# WLAN_BLUETOOTH.net
KiCad netlist of a schematic drawn in Altium Designer
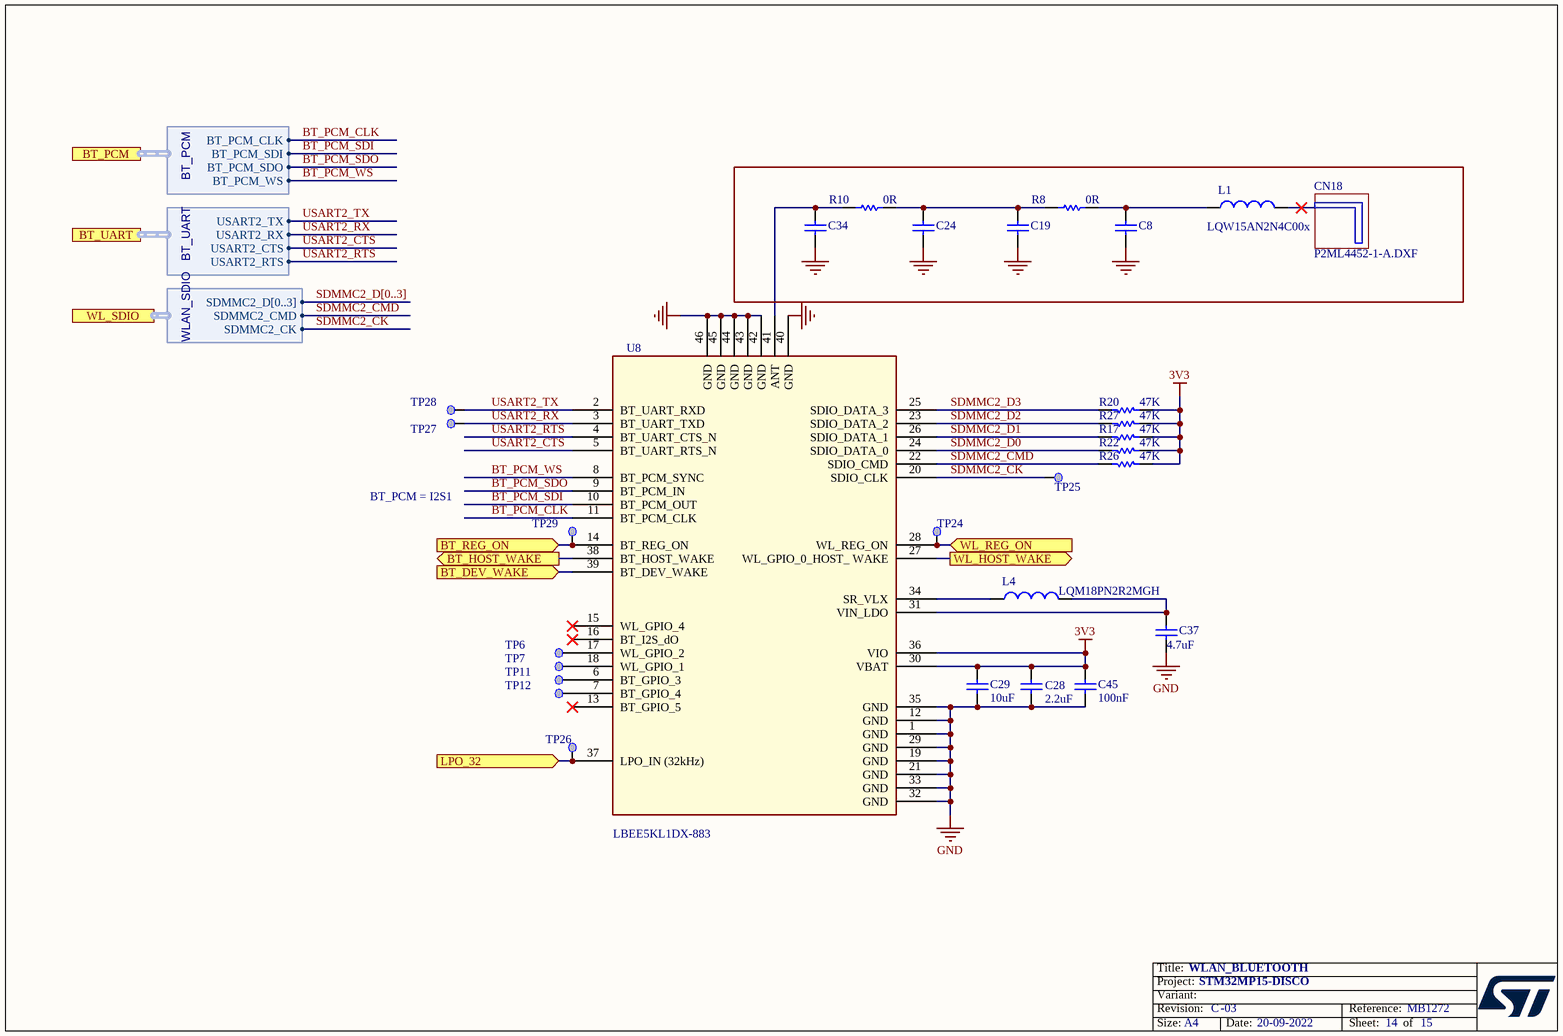
[diagram p0: WLAN_BLUETOOTH.SchDoc]

(export (version "E")
  (design (tool "Eeschema 10.0.6"))
  (components
    (comp (ref "C8")
      (value "Capacitor")
      (footprint "C0402")
      (description "Capacitor, MLCC, 12pF, 50V, NPO, 5%, 0402, T=0,5mm")
      (fields
        (field (name "INTERNAL_PART_NUMBER") "MCD-00200")
        (field (name "MANUFACTURER_PART_NUMBER") "CC0402JRNPO9BN120")
        (field (name "PROVIDED_BY") "SUBCO")
      )
      (libsource (lib "MCD_PARTS_database") (part "Capacitor"))
    )
    (comp (ref "C19")
      (value "Capacitor")
      (footprint "C0402")
      (description "Capacitor, MLCC, 12pF, 50V, NPO, 5%, 0402, T=0,5mm")
      (fields
        (field (name "INTERNAL_PART_NUMBER") "MCD-00200")
        (field (name "MANUFACTURER_PART_NUMBER") "CC0402JRNPO9BN120")
        (field (name "PROVIDED_BY") "SUBCO")
      )
      (libsource (lib "MCD_PARTS_database") (part "Capacitor"))
    )
    (comp (ref "C24")
      (value "Capacitor")
      (footprint "C0402")
      (description "Capacitor, MLCC, 12pF, 50V, NPO, 5%, 0402, T=0,5mm")
      (fields
        (field (name "INTERNAL_PART_NUMBER") "MCD-00200")
        (field (name "MANUFACTURER_PART_NUMBER") "CC0402JRNPO9BN120")
        (field (name "PROVIDED_BY") "SUBCO")
      )
      (libsource (lib "MCD_PARTS_database") (part "Capacitor"))
    )
    (comp (ref "C28")
      (value "2.2uF")
      (footprint "C0603")
      (description "Capacitor, MLCC, 2.2uF, 10V, X5R, 10%, 0603, T=0,8mm")
      (fields
        (field (name "INTERNAL_PART_NUMBER") "MCD-00012")
        (field (name "MANUFACTURER_PART_NUMBER") "CC0603KRX5R6BB225")
        (field (name "PROVIDED_BY") "SUBCO")
      )
      (libsource (lib "MCD_PARTS_database") (part "Capacitor"))
    )
    (comp (ref "C29")
      (value "10uF")
      (footprint "C0603")
      (description "Capacitor, MLCC, 10uF, 10V, X5R, 10%, 0603, T=0,8mm")
      (fields
        (field (name "INTERNAL_PART_NUMBER") "MCD-00099")
        (field (name "MANUFACTURER_PART_NUMBER") "GRM188R61A106KE69D")
        (field (name "PROVIDED_BY") "SUBCO")
      )
      (libsource (lib "MCD_PARTS_database") (part "Capacitor"))
    )
    (comp (ref "C34")
      (value "Capacitor")
      (footprint "C0402")
      (description "Capacitor, MLCC, 12pF, 50V, NPO, 5%, 0402, T=0,5mm")
      (fields
        (field (name "INTERNAL_PART_NUMBER") "MCD-00200")
        (field (name "MANUFACTURER_PART_NUMBER") "CC0402JRNPO9BN120")
        (field (name "PROVIDED_BY") "SUBCO")
      )
      (libsource (lib "MCD_PARTS_database") (part "Capacitor"))
    )
    (comp (ref "C37")
      (value "4.7uF")
      (footprint "C0402")
      (description "Capacitor, MLCC, 4.7uF, 6V3, X5R, 20%, 0402, T=0,5mm")
      (fields
        (field (name "INTERNAL_PART_NUMBER") "MCD-01356")
        (field (name "MANUFACTURER_PART_NUMBER") "GRM155R60J475ME47")
        (field (name "PROVIDED_BY") "SUBCO")
      )
      (libsource (lib "MCD_PARTS_database") (part "Capacitor"))
    )
    (comp (ref "C45")
      (value "100nF")
      (footprint "C0402")
      (description "Capacitor,100nF,16V,X7R,10%,0402")
      (fields
        (field (name "INTERNAL_PART_NUMBER") "MCD-00006")
        (field (name "MANUFACTURER_PART_NUMBER") "CC0402KRX7R7BB104")
        (field (name "PROVIDED_BY") "SUBCO")
      )
      (libsource (lib "MCD_PARTS_database") (part "Capacitor"))
    )
    (comp (ref "CN18")
      (value "P2ML4452-1-A.DXF")
      (footprint "ANT_MURATA_TYPE-1-DX_P2ML4452-1-A_DXF")
      (description "Murata_Type1DX_AntennaDesign_P2ML4452-1-A.DXF")
      (fields
        (field (name "INTERNAL_PART_NUMBER") "MCD-00656")
        (field (name "MANUFACTURER_PART_NUMBER") "Antenna design")
      )
      (libsource (lib "MCD_PARTS_database") (part "antenna_Wifi_BLE_Murata"))
    )
    (comp (ref "L1")
      (value "LQW15AN2N4C00x")
      (footprint "IND_0402_MURATA_LQW15AN2N4C00X")
      (description "Inductor,2.4nH,+-0.2nH,0.05R,0.85A,0402")
      (fields
        (field (name "INTERNAL_PART_NUMBER") "MCD-00657")
        (field (name "MANUFACTURER") "MURATA")
        (field (name "PROVIDED_BY") "SUBCO")
      )
      (libsource (lib "MCD_PARTS_database") (part "Inductor"))
    )
    (comp (ref "L4")
      (value "LQM18PN2R2MGH")
      (footprint "L0603")
      (description "Inductor, 2.2µH, 20%, Isat 0.35A, DCR 0.2Ohm, 0603")
      (fields
        (field (name "INTERNAL_PART_NUMBER") "MCD-00659")
        (field (name "MANUFACTURER") "MURATA")
        (field (name "PROVIDED_BY") "SUBCO")
      )
      (libsource (lib "MCD_PARTS_database") (part "Inductor"))
    )
    (comp (ref "R8")
      (value "0R")
      (footprint "R0402")
      (description "Resistor,0R,0402,5%,1/16W")
      (fields
        (field (name "INTERNAL_PART_NUMBER") "MCD-00052")
        (field (name "MANUFACTURER_PART_NUMBER") "RC0402JR-070RL")
        (field (name "PROVIDED_BY") "SUBCO")
      )
      (libsource (lib "MCD_PARTS_database") (part "Resistor"))
    )
    (comp (ref "R10")
      (value "0R")
      (footprint "R0402")
      (description "Resistor,0R,0402,5%,1/16W")
      (fields
        (field (name "INTERNAL_PART_NUMBER") "MCD-00052")
        (field (name "MANUFACTURER_PART_NUMBER") "RC0402JR-070RL")
        (field (name "PROVIDED_BY") "SUBCO")
      )
      (libsource (lib "MCD_PARTS_database") (part "Resistor"))
    )
    (comp (ref "R17")
      (value "47K")
      (footprint "R0402")
      (description "Resistor,47K,0402,1%,1/16W")
      (fields
        (field (name "INTERNAL_PART_NUMBER") "MCD-00063")
        (field (name "MANUFACTURER_PART_NUMBER") "RC0402FR-0747KL")
        (field (name "PROVIDED_BY") "SUBCO")
      )
      (libsource (lib "MCD_PARTS_database") (part "Resistor"))
    )
    (comp (ref "R20")
      (value "47K")
      (footprint "R0402")
      (description "Resistor,47K,0402,1%,1/16W")
      (fields
        (field (name "INTERNAL_PART_NUMBER") "MCD-00063")
        (field (name "MANUFACTURER_PART_NUMBER") "RC0402FR-0747KL")
        (field (name "PROVIDED_BY") "SUBCO")
      )
      (libsource (lib "MCD_PARTS_database") (part "Resistor"))
    )
    (comp (ref "R22")
      (value "47K")
      (footprint "R0402")
      (description "Resistor,47K,0402,1%,1/16W")
      (fields
        (field (name "INTERNAL_PART_NUMBER") "MCD-00063")
        (field (name "MANUFACTURER_PART_NUMBER") "RC0402FR-0747KL")
        (field (name "PROVIDED_BY") "SUBCO")
      )
      (libsource (lib "MCD_PARTS_database") (part "Resistor"))
    )
    (comp (ref "R26")
      (value "47K")
      (footprint "R0402")
      (description "Resistor,47K,0402,1%,1/16W")
      (fields
        (field (name "INTERNAL_PART_NUMBER") "MCD-00063")
        (field (name "MANUFACTURER_PART_NUMBER") "RC0402FR-0747KL")
        (field (name "PROVIDED_BY") "SUBCO")
      )
      (libsource (lib "MCD_PARTS_database") (part "Resistor"))
    )
    (comp (ref "R27")
      (value "47K")
      (footprint "R0402")
      (description "Resistor,47K,0402,1%,1/16W")
      (fields
        (field (name "INTERNAL_PART_NUMBER") "MCD-00063")
        (field (name "MANUFACTURER_PART_NUMBER") "RC0402FR-0747KL")
        (field (name "PROVIDED_BY") "SUBCO")
      )
      (libsource (lib "MCD_PARTS_database") (part "Resistor"))
    )
    (comp (ref "TP6")
      (value "Test Point")
      (footprint "TP_SMD_1MM")
      (description "Test Point 1mm")
      (fields
        (field (name "INTERNAL_PART_NUMBER") "MCD-00074")
        (field (name "MANUFACTURER_PART_NUMBER") "n/a")
      )
      (libsource (lib "MCD_PARTS_database") (part "Test Point"))
    )
    (comp (ref "TP7")
      (value "Test Point")
      (footprint "TP_SMD_1MM")
      (description "Test Point 1mm")
      (fields
        (field (name "INTERNAL_PART_NUMBER") "MCD-00074")
        (field (name "MANUFACTURER_PART_NUMBER") "n/a")
      )
      (libsource (lib "MCD_PARTS_database") (part "Test Point"))
    )
    (comp (ref "TP11")
      (value "Test Point")
      (footprint "TP_SMD_1MM")
      (description "Test Point 1mm")
      (fields
        (field (name "INTERNAL_PART_NUMBER") "MCD-00074")
        (field (name "MANUFACTURER_PART_NUMBER") "n/a")
      )
      (libsource (lib "MCD_PARTS_database") (part "Test Point"))
    )
    (comp (ref "TP12")
      (value "Test Point")
      (footprint "TP_SMD_1MM")
      (description "Test Point 1mm")
      (fields
        (field (name "INTERNAL_PART_NUMBER") "MCD-00074")
        (field (name "MANUFACTURER_PART_NUMBER") "n/a")
      )
      (libsource (lib "MCD_PARTS_database") (part "Test Point"))
    )
    (comp (ref "TP24")
      (value "Test Point")
      (footprint "TP_SMD_0-6MM")
      (description "Test Point 0.6mm")
      (fields (field (name "INTERNAL_PART_NUMBER") "MCD-00631"))
      (libsource (lib "") (part "Test Point_1"))
    )
    (comp (ref "TP25")
      (value "Test Point")
      (footprint "TP_SMD_0-6MM")
      (description "Test Point 0.6mm")
      (fields (field (name "INTERNAL_PART_NUMBER") "MCD-00631"))
      (libsource (lib "") (part "Test Point_2"))
    )
    (comp (ref "TP26")
      (value "Test Point")
      (footprint "TP_SMD_0-6MM")
      (description "Test Point 0.6mm")
      (fields (field (name "INTERNAL_PART_NUMBER") "MCD-00631"))
      (libsource (lib "") (part "Test Point_1"))
    )
    (comp (ref "TP27")
      (value "Test Point")
      (footprint "TP_SMD_0-6MM")
      (description "Test Point 0.6mm")
      (fields (field (name "INTERNAL_PART_NUMBER") "MCD-00631"))
      (libsource (lib "MCD_PARTS_database") (part "Test Point"))
    )
    (comp (ref "TP28")
      (value "Test Point")
      (footprint "TP_SMD_0-6MM")
      (description "Test Point 0.6mm")
      (fields (field (name "INTERNAL_PART_NUMBER") "MCD-00631"))
      (libsource (lib "MCD_PARTS_database") (part "Test Point"))
    )
    (comp (ref "TP29")
      (value "Test Point")
      (footprint "TP_SMD_0-6MM")
      (description "Test Point 0.6mm")
      (fields (field (name "INTERNAL_PART_NUMBER") "MCD-00631"))
      (libsource (lib "") (part "Test Point_1"))
    )
    (comp (ref "U8")
      (value "LBEE5KL1DX-883")
      (footprint "MOD_WLAN-BT_MURATA_LBEE5KL1DX-883")
      (description "IEEE802.11b/g/n W-LAN + Bluetooth 4.1+EDR module")
      (fields
        (field (name "INTERNAL_PART_NUMBER") "MCD-00268")
        (field (name "MANUFACTURER") "MURATA")
        (field (name "PROVIDED_BY") "SUBCO")
      )
      (libsource (lib "MCD_PARTS_database") (part "LBEE5KL1DX-883"))
    )
  )
  (nets
    (net (code "4") (name "/BT_DEV_WAKE") (class "Default")
      (node (ref "U8") (pin "39") (pinfunction "BT_DEV_WAKE_39") (pintype "passive"))
    )
    (net (code "5") (name "/BT_HOST_WAKE") (class "Default")
      (node (ref "U8") (pin "38") (pinfunction "BT_HOST_WAKE_38") (pintype "passive"))
    )
    (net (code "6") (name "/BT_PCM_CLK") (class "Default")
      (node (ref "U8") (pin "11") (pinfunction "BT_PCM_CLK_11") (pintype "passive"))
    )
    (net (code "7") (name "/BT_PCM_SDI") (class "Default")
      (node (ref "U8") (pin "10") (pinfunction "BT_PCM_OUT_10") (pintype "passive"))
    )
    (net (code "8") (name "/BT_PCM_SDO") (class "Default")
      (node (ref "U8") (pin "9") (pinfunction "BT_PCM_IN_9") (pintype "passive"))
    )
    (net (code "9") (name "/BT_PCM_WS") (class "Default")
      (node (ref "U8") (pin "8") (pinfunction "BT_PCM_SYNC_8") (pintype "passive"))
    )
    (net (code "10") (name "/BT_REG_ON") (class "Default")
      (node (ref "TP29") (pin "1") (pinfunction "1_1") (pintype "passive"))
      (node (ref "U8") (pin "14") (pinfunction "BT_REG_ON_14") (pintype "passive"))
    )
    (net (code "11") (name "/LPO_32") (class "Default")
      (node (ref "TP26") (pin "1") (pinfunction "1_1") (pintype "passive"))
      (node (ref "U8") (pin "37") (pinfunction "LPO_IN_(32kHz)_37") (pintype "passive"))
    )
    (net (code "12") (name "/SDMMC2_CK") (class "Default")
      (node (ref "TP25") (pin "1") (pinfunction "1_1") (pintype "passive"))
      (node (ref "U8") (pin "20") (pinfunction "SDIO_CLK_20") (pintype "passive"))
    )
    (net (code "13") (name "/SDMMC2_CMD") (class "Default")
      (node (ref "R26") (pin "2") (pinfunction "2_2") (pintype "passive"))
      (node (ref "U8") (pin "22") (pinfunction "SDIO_CMD_22") (pintype "passive"))
    )
    (net (code "14") (name "/SDMMC2_D0") (class "Default")
      (node (ref "R22") (pin "2") (pinfunction "2_2") (pintype "passive"))
      (node (ref "U8") (pin "24") (pinfunction "SDIO_DATA_0_24") (pintype "passive"))
    )
    (net (code "15") (name "/SDMMC2_D1") (class "Default")
      (node (ref "R17") (pin "2") (pinfunction "2_2") (pintype "passive"))
      (node (ref "U8") (pin "26") (pinfunction "SDIO_DATA_1_26") (pintype "passive"))
    )
    (net (code "16") (name "/SDMMC2_D2") (class "Default")
      (node (ref "R27") (pin "2") (pinfunction "2_2") (pintype "passive"))
      (node (ref "U8") (pin "23") (pinfunction "SDIO_DATA_2_23") (pintype "passive"))
    )
    (net (code "17") (name "/SDMMC2_D3") (class "Default")
      (node (ref "R20") (pin "2") (pinfunction "2_2") (pintype "passive"))
      (node (ref "U8") (pin "25") (pinfunction "SDIO_DATA_3_25") (pintype "passive"))
    )
    (net (code "19") (name "/USART2_CTS") (class "Default")
      (node (ref "U8") (pin "5") (pinfunction "BT_UART_RTS_N_5") (pintype "passive"))
    )
    (net (code "20") (name "/USART2_RTS") (class "Default")
      (node (ref "U8") (pin "4") (pinfunction "BT_UART_CTS_N_4") (pintype "passive"))
    )
    (net (code "21") (name "/USART2_RX") (class "Default")
      (node (ref "TP27") (pin "1") (pinfunction "1_1") (pintype "passive"))
      (node (ref "U8") (pin "3") (pinfunction "BT_UART_TXD_3") (pintype "passive"))
    )
    (net (code "22") (name "/USART2_TX") (class "Default")
      (node (ref "TP28") (pin "1") (pinfunction "1_1") (pintype "passive"))
      (node (ref "U8") (pin "2") (pinfunction "BT_UART_RXD_2") (pintype "passive"))
    )
    (net (code "23") (name "/WL_HOST_WAKE") (class "Default")
      (node (ref "U8") (pin "27") (pinfunction "WL_GPIO_0_HOST__WAKE_27") (pintype "passive"))
    )
    (net (code "24") (name "/WL_REG_ON") (class "Default")
      (node (ref "TP24") (pin "1") (pinfunction "1_1") (pintype "passive"))
      (node (ref "U8") (pin "28") (pinfunction "WL_REG_ON_28") (pintype "passive"))
    )
    (net (code "28") (name "3V3") (class "Default")
      (node (ref "C28") (pin "2") (pinfunction "2_2") (pintype "passive"))
      (node (ref "C29") (pin "2") (pinfunction "2_2") (pintype "passive"))
      (node (ref "C45") (pin "2") (pinfunction "2_2") (pintype "passive"))
      (node (ref "R17") (pin "1") (pinfunction "1_1") (pintype "passive"))
      (node (ref "R20") (pin "1") (pinfunction "1_1") (pintype "passive"))
      (node (ref "R22") (pin "1") (pinfunction "1_1") (pintype "passive"))
      (node (ref "R26") (pin "1") (pinfunction "1_1") (pintype "passive"))
      (node (ref "R27") (pin "1") (pinfunction "1_1") (pintype "passive"))
      (node (ref "U8") (pin "30") (pinfunction "VBAT_30") (pintype "passive"))
      (node (ref "U8") (pin "36") (pinfunction "VIO_36") (pintype "passive"))
    )
    (net (code "29") (name "GND") (class "Default")
      (node (ref "C19") (pin "1") (pinfunction "1_1") (pintype "passive"))
      (node (ref "C24") (pin "1") (pinfunction "1_1") (pintype "passive"))
      (node (ref "C28") (pin "1") (pinfunction "1_1") (pintype "passive"))
      (node (ref "C29") (pin "1") (pinfunction "1_1") (pintype "passive"))
      (node (ref "C34") (pin "1") (pinfunction "1_1") (pintype "passive"))
      (node (ref "C37") (pin "1") (pinfunction "1_1") (pintype "passive"))
      (node (ref "C45") (pin "1") (pinfunction "1_1") (pintype "passive"))
      (node (ref "C8") (pin "1") (pinfunction "1_1") (pintype "passive"))
      (node (ref "U8") (pin "1") (pinfunction "GND_1") (pintype "passive"))
      (node (ref "U8") (pin "12") (pinfunction "GND_12") (pintype "passive"))
      (node (ref "U8") (pin "19") (pinfunction "GND_19") (pintype "passive"))
      (node (ref "U8") (pin "21") (pinfunction "GND_21") (pintype "passive"))
      (node (ref "U8") (pin "29") (pinfunction "GND_29") (pintype "passive"))
      (node (ref "U8") (pin "32") (pinfunction "GND_32") (pintype "passive"))
      (node (ref "U8") (pin "33") (pinfunction "GND_33") (pintype "passive"))
      (node (ref "U8") (pin "35") (pinfunction "GND_35") (pintype "passive"))
      (node (ref "U8") (pin "40") (pinfunction "GND_40") (pintype "passive"))
      (node (ref "U8") (pin "42") (pinfunction "GND_42") (pintype "passive"))
      (node (ref "U8") (pin "43") (pinfunction "GND_43") (pintype "passive"))
      (node (ref "U8") (pin "44") (pinfunction "GND_44") (pintype "passive"))
      (node (ref "U8") (pin "45") (pinfunction "GND_45") (pintype "passive"))
      (node (ref "U8") (pin "46") (pinfunction "GND_46") (pintype "passive"))
    )
    (net (code "30") (name "Net-(C8-Pad2)") (class "Default")
      (node (ref "C8") (pin "2") (pinfunction "2_2") (pintype "passive"))
      (node (ref "L1") (pin "1") (pinfunction "1_1") (pintype "passive"))
      (node (ref "R8") (pin "1") (pinfunction "1_1") (pintype "passive"))
    )
    (net (code "31") (name "Net-(C19-Pad2)") (class "Default")
      (node (ref "C19") (pin "2") (pinfunction "2_2") (pintype "passive"))
      (node (ref "C24") (pin "2") (pinfunction "2_2") (pintype "passive"))
      (node (ref "R10") (pin "1") (pinfunction "1_1") (pintype "passive"))
      (node (ref "R8") (pin "2") (pinfunction "2_2") (pintype "passive"))
    )
    (net (code "32") (name "Net-(U8-ANT)") (class "Default")
      (node (ref "C34") (pin "2") (pinfunction "2_2") (pintype "passive"))
      (node (ref "R10") (pin "2") (pinfunction "2_2") (pintype "passive"))
      (node (ref "U8") (pin "41") (pinfunction "ANT_41") (pintype "passive"))
    )
    (net (code "33") (name "Net-(U8-BT_GPIO_3)") (class "Default")
      (node (ref "TP11") (pin "1") (pinfunction "1_1") (pintype "passive"))
      (node (ref "U8") (pin "6") (pinfunction "BT_GPIO_3_6") (pintype "passive"))
    )
    (net (code "34") (name "Net-(U8-BT_GPIO_4)") (class "Default")
      (node (ref "TP12") (pin "1") (pinfunction "1_1") (pintype "passive"))
      (node (ref "U8") (pin "7") (pinfunction "BT_GPIO_4_7") (pintype "passive"))
    )
    (net (code "35") (name "Net-(U8-SR_VLX)") (class "Default")
      (node (ref "L4") (pin "1") (pinfunction "1_1") (pintype "passive"))
      (node (ref "U8") (pin "34") (pinfunction "SR_VLX_34") (pintype "passive"))
    )
    (net (code "36") (name "Net-(U8-VIN_LDO)") (class "Default")
      (node (ref "C37") (pin "2") (pinfunction "2_2") (pintype "passive"))
      (node (ref "L4") (pin "2") (pinfunction "2_2") (pintype "passive"))
      (node (ref "U8") (pin "31") (pinfunction "VIN_LDO_31") (pintype "passive"))
    )
    (net (code "37") (name "Net-(U8-WL_GPIO_1)") (class "Default")
      (node (ref "TP7") (pin "1") (pinfunction "1_1") (pintype "passive"))
      (node (ref "U8") (pin "18") (pinfunction "WL_GPIO_1_18") (pintype "passive"))
    )
    (net (code "38") (name "Net-(U8-WL_GPIO_2)") (class "Default")
      (node (ref "TP6") (pin "1") (pinfunction "1_1") (pintype "passive"))
      (node (ref "U8") (pin "17") (pinfunction "WL_GPIO_2_17") (pintype "passive"))
    )
    (net (code "39") (name "unconnected-(L1-Pad2)") (class "Default")
      (node (ref "L1") (pin "2") (pinfunction "2_2") (pintype "passive"))
    )
    (net (code "40") (name "unconnected-(U8-BT_GPIO_5-Pad13)") (class "Default")
      (node (ref "U8") (pin "13") (pinfunction "BT_GPIO_5_13") (pintype "passive+no_connect"))
    )
    (net (code "41") (name "unconnected-(U8-BT_I2S_dO-Pad16)") (class "Default")
      (node (ref "U8") (pin "16") (pinfunction "BT_I2S_dO_16") (pintype "passive+no_connect"))
    )
    (net (code "42") (name "unconnected-(U8-WL_GPIO_4-Pad15)") (class "Default")
      (node (ref "U8") (pin "15") (pinfunction "WL_GPIO_4_15") (pintype "passive+no_connect"))
    )
  )
)
